# POWER.net
KiCad netlist of a schematic drawn in Altium Designer
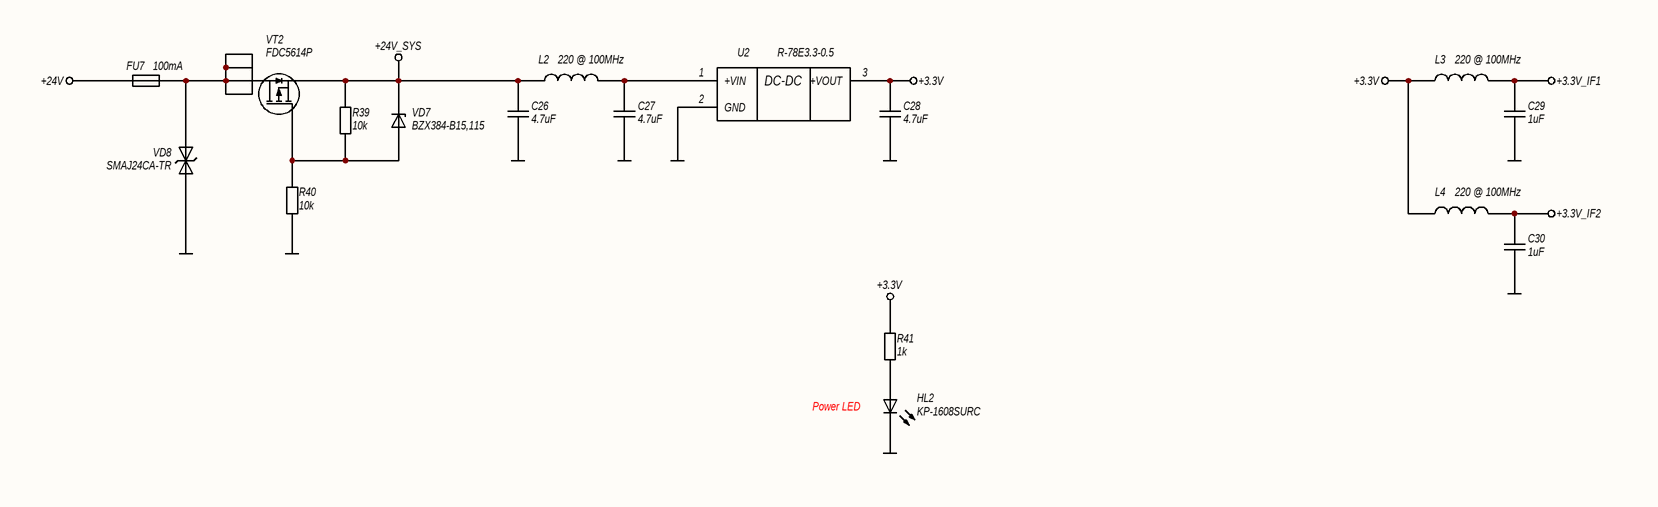
[diagram p0: POWER.SchDoc]

(export (version "E")
  (design (tool "Eeschema 10.0.6"))
  (components
    (comp (ref "C26")
      (value "4.7uF")
      (footprint "C1206N")
      (description "Конденсатор")
      (libsource (lib "Components Library") (part "CAP_FIXED"))
    )
    (comp (ref "C27")
      (value "4.7uF")
      (footprint "C1206N")
      (description "Конденсатор")
      (libsource (lib "Components Library") (part "CAP_FIXED"))
    )
    (comp (ref "C28")
      (value "4.7uF")
      (footprint "C0805N")
      (description "Конденсатор")
      (libsource (lib "Components Library") (part "CAP_FIXED"))
    )
    (comp (ref "C29")
      (value "1uF")
      (footprint "C0603N")
      (description "Конденсатор")
      (libsource (lib "Components Library") (part "CAP_FIXED"))
    )
    (comp (ref "C30")
      (value "1uF")
      (footprint "C0603N")
      (description "Конденсатор")
      (libsource (lib "Components Library") (part "CAP_FIXED"))
    )
    (comp (ref "FU7")
      (value "100mA")
      (footprint "0ZCJ_0.85")
      (description "Плавкий предохранитель")
      (libsource (lib "Components Library") (part "FUSE"))
    )
    (comp (ref "HL2")
      (value "KP-1608SURC")
      (footprint "LED0603")
      (description "Светодиод")
      (libsource (lib "Components Library") (part "LED"))
    )
    (comp (ref "L2")
      (value "220 @ 100MHz")
      (footprint "FB0603N")
      (description "Фильтр ЭМП индуктивный")
      (libsource (lib "Components Library") (part "IND_FILTER"))
    )
    (comp (ref "L3")
      (value "220 @ 100MHz")
      (footprint "FB0603N")
      (description "Фильтр ЭМП индуктивный")
      (libsource (lib "Components Library") (part "IND_FILTER"))
    )
    (comp (ref "L4")
      (value "220 @ 100MHz")
      (footprint "FB0603N")
      (description "Фильтр ЭМП индуктивный")
      (libsource (lib "Components Library") (part "IND_FILTER"))
    )
    (comp (ref "R39")
      (value "10k")
      (footprint "R0603N")
      (description "Резистор")
      (libsource (lib "Components Library") (part "RES_FIXED"))
    )
    (comp (ref "R40")
      (value "10k")
      (footprint "R0603N")
      (description "Резистор")
      (libsource (lib "Components Library") (part "RES_FIXED"))
    )
    (comp (ref "R41")
      (value "1k")
      (footprint "R0603N")
      (description "Резистор")
      (libsource (lib "Components Library") (part "RES_FIXED"))
    )
    (comp (ref "U2")
      (value "R-78E3.3-0.5")
      (footprint "DC-DC_SIP3")
      (description "Модуль неизолированного DC-DC конвертера")
      (libsource (lib "Components Library") (part "DC-DC_SIP3"))
    )
    (comp (ref "VD7")
      (value "BZX384-B15,115")
      (footprint "SOD323")
      (description "Стабилитрон")
      (libsource (lib "Components Library") (part "ZENER"))
    )
    (comp (ref "VD8")
      (value "SMAJ24CA-TR")
      (footprint "SMA")
      (description "TVS диод двунаправленный")
      (libsource (lib "Components Library") (part "TVS_BIDIR"))
    )
    (comp (ref "VT2")
      (value "FDC5614P")
      (footprint "TSOT23-6")
      (description "МОП транзистор, P-канальный")
      (libsource (lib "Components Library") (part "P-MOS 6 LEADS_G3"))
    )
  )
  (nets
    (net (code "1") (name "+3.3V") (class "Default")
      (node (ref "C28") (pin "2") (pinfunction "2_2") (pintype "passive"))
      (node (ref "L3") (pin "1") (pinfunction "1_1") (pintype "passive"))
      (node (ref "L4") (pin "1") (pinfunction "1_1") (pintype "passive"))
      (node (ref "R41") (pin "1") (pinfunction "1_1") (pintype "passive"))
      (node (ref "U2") (pin "3") (pinfunction "+VOUT_3") (pintype "power_in"))
    )
    (net (code "2") (name "+3.3V_IF1") (class "Default")
      (node (ref "C29") (pin "1") (pinfunction "1_1") (pintype "passive"))
      (node (ref "L3") (pin "2") (pinfunction "2_2") (pintype "passive"))
    )
    (net (code "3") (name "+3.3V_IF2") (class "Default")
      (node (ref "C30") (pin "1") (pinfunction "1_1") (pintype "passive"))
      (node (ref "L4") (pin "2") (pinfunction "2_2") (pintype "passive"))
    )
    (net (code "4") (name "+24V") (class "Default")
      (node (ref "FU7") (pin "2") (pinfunction "2_2") (pintype "passive"))
    )
    (net (code "5") (name "+24V_SYS") (class "Default")
      (node (ref "C26") (pin "1") (pinfunction "1_1") (pintype "passive"))
      (node (ref "L2") (pin "1") (pinfunction "1_1") (pintype "passive"))
      (node (ref "R39") (pin "1") (pinfunction "1_1") (pintype "passive"))
      (node (ref "VD7") (pin "1") (pinfunction "K_1") (pintype "passive"))
      (node (ref "VT2") (pin "4") (pinfunction "S_4") (pintype "passive"))
    )
    (net (code "6") (name "GND") (class "Default")
      (node (ref "C26") (pin "2") (pinfunction "2_2") (pintype "passive"))
      (node (ref "C27") (pin "2") (pinfunction "2_2") (pintype "passive"))
      (node (ref "C28") (pin "1") (pinfunction "1_1") (pintype "passive"))
      (node (ref "C29") (pin "2") (pinfunction "2_2") (pintype "passive"))
      (node (ref "C30") (pin "2") (pinfunction "2_2") (pintype "passive"))
      (node (ref "HL2") (pin "1") (pinfunction "K_1") (pintype "passive"))
      (node (ref "R40") (pin "2") (pinfunction "2_2") (pintype "passive"))
      (node (ref "U2") (pin "2") (pinfunction "GND_2") (pintype "power_in"))
      (node (ref "VD8") (pin "2") (pinfunction "A2_2") (pintype "passive"))
    )
    (net (code "7") (name "Net-(HL2-A)") (class "Default")
      (node (ref "HL2") (pin "2") (pinfunction "A_2") (pintype "passive"))
      (node (ref "R41") (pin "2") (pinfunction "2_2") (pintype "passive"))
    )
    (net (code "8") (name "Net-(U2-+VIN)") (class "Default")
      (node (ref "C27") (pin "1") (pinfunction "1_1") (pintype "passive"))
      (node (ref "L2") (pin "2") (pinfunction "2_2") (pintype "passive"))
      (node (ref "U2") (pin "1") (pinfunction "+VIN_1") (pintype "power_in"))
    )
    (net (code "9") (name "Net-(VD7-A)") (class "Default")
      (node (ref "R39") (pin "2") (pinfunction "2_2") (pintype "passive"))
      (node (ref "R40") (pin "1") (pinfunction "1_1") (pintype "passive"))
      (node (ref "VD7") (pin "2") (pinfunction "A_2") (pintype "passive"))
      (node (ref "VT2") (pin "3") (pinfunction "G_3") (pintype "passive"))
    )
    (net (code "10") (name "Net-(VD8-A1)") (class "Default")
      (node (ref "FU7") (pin "1") (pinfunction "1_1") (pintype "passive"))
      (node (ref "VD8") (pin "1") (pinfunction "A1_1") (pintype "passive"))
      (node (ref "VT2") (pin "1") (pinfunction "D_1") (pintype "passive"))
      (node (ref "VT2") (pin "2") (pinfunction "D_2") (pintype "passive"))
      (node (ref "VT2") (pin "5") (pinfunction "D_5") (pintype "passive"))
      (node (ref "VT2") (pin "6") (pinfunction "D_6") (pintype "passive"))
    )
  )
)
